# schBeagleBone.net
KiCad netlist of a schematic drawn in Altium Designer
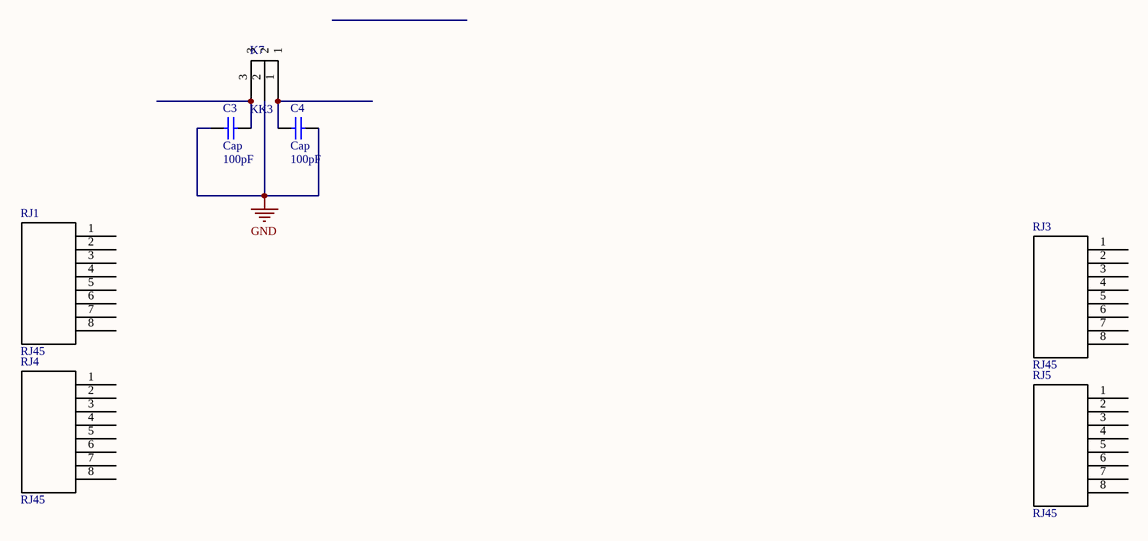
[diagram p0: schBeagleBone.SchDoc]

(export (version "E")
  (design (tool "Eeschema 10.0.6"))
  (components
    (comp (ref "C3")
      (value "Cap")
      (footprint "RAD-0.3")
      (description "Capacitor")
      (fields (field (name "ALTIUM_VALUE") "100pF") (field (name "PUBLISHER") "Altium Limited"))
      (libsource (lib "Miscellaneous Devices") (part "Cap"))
    )
    (comp (ref "C4")
      (value "Cap")
      (footprint "RAD-0.3")
      (description "Capacitor")
      (fields (field (name "ALTIUM_VALUE") "100pF") (field (name "PUBLISHER") "Altium Limited"))
      (libsource (lib "Miscellaneous Devices") (part "Cap"))
    )
    (comp (ref "K7") (value "KK3") (footprint "3-vias") (libsource (lib "Componentes_Open") (part "KK3Vias")))
    (comp (ref "RJ1")
      (value "RJ45")
      (footprint "RJ45_90")
      (libsource (lib "Componentes_Open") (part "RJ45_90"))
    )
    (comp (ref "RJ3")
      (value "RJ45")
      (footprint "RJ45_Simples")
      (libsource (lib "Componentes_Open") (part "RJ45"))
    )
    (comp (ref "RJ4")
      (value "RJ45")
      (footprint "RJ45_90")
      (libsource (lib "Componentes_Open") (part "RJ45_90"))
    )
    (comp (ref "RJ5")
      (value "RJ45")
      (footprint "RJ45_Simples")
      (libsource (lib "Componentes_Open") (part "RJ45"))
    )
  )
  (nets
    (net (code "1") (name "GND") (class "Default")
      (node (ref "C3") (pin "1") (pinfunction "1_1") (pintype "passive"))
      (node (ref "C4") (pin "2") (pinfunction "2_2") (pintype "passive"))
      (node (ref "K7") (pin "2") (pinfunction "2_2") (pintype "passive"))
    )
    (net (code "2") (name "Net-(C3-Pad2)") (class "Default")
      (node (ref "C3") (pin "2") (pinfunction "2_2") (pintype "passive"))
      (node (ref "K7") (pin "3") (pinfunction "3_3") (pintype "passive"))
    )
    (net (code "3") (name "Net-(C4-Pad1)") (class "Default")
      (node (ref "C4") (pin "1") (pinfunction "1_1") (pintype "passive"))
      (node (ref "K7") (pin "1") (pinfunction "1_1") (pintype "passive"))
    )
    (net (code "4") (name "unconnected-(RJ1-9-Pad1)") (class "Default")
      (node (ref "RJ1") (pin "1") (pinfunction "9_1") (pintype "passive"))
    )
    (net (code "5") (name "unconnected-(RJ1-Pad2)") (class "Default")
      (node (ref "RJ1") (pin "2") (pinfunction "2_2") (pintype "passive"))
    )
    (net (code "6") (name "unconnected-(RJ1-Pad3)") (class "Default")
      (node (ref "RJ1") (pin "3") (pinfunction "3_3") (pintype "passive"))
    )
    (net (code "7") (name "unconnected-(RJ1-Pad4)") (class "Default")
      (node (ref "RJ1") (pin "4") (pinfunction "4_4") (pintype "passive"))
    )
    (net (code "8") (name "unconnected-(RJ1-Pad5)") (class "Default")
      (node (ref "RJ1") (pin "5") (pinfunction "5_5") (pintype "passive"))
    )
    (net (code "9") (name "unconnected-(RJ1-Pad6)") (class "Default")
      (node (ref "RJ1") (pin "6") (pinfunction "6_6") (pintype "passive"))
    )
    (net (code "10") (name "unconnected-(RJ1-Pad7)") (class "Default")
      (node (ref "RJ1") (pin "7") (pinfunction "7_7") (pintype "passive"))
    )
    (net (code "11") (name "unconnected-(RJ1-Pad8)") (class "Default")
      (node (ref "RJ1") (pin "8") (pinfunction "8_8") (pintype "passive"))
    )
    (net (code "12") (name "unconnected-(RJ3-9-Pad1)") (class "Default")
      (node (ref "RJ3") (pin "1") (pinfunction "9_1") (pintype "passive"))
    )
    (net (code "13") (name "unconnected-(RJ3-Pad2)") (class "Default")
      (node (ref "RJ3") (pin "2") (pinfunction "2_2") (pintype "passive"))
    )
    (net (code "14") (name "unconnected-(RJ3-Pad3)") (class "Default")
      (node (ref "RJ3") (pin "3") (pinfunction "3_3") (pintype "passive"))
    )
    (net (code "15") (name "unconnected-(RJ3-Pad4)") (class "Default")
      (node (ref "RJ3") (pin "4") (pinfunction "4_4") (pintype "passive"))
    )
    (net (code "16") (name "unconnected-(RJ3-Pad5)") (class "Default")
      (node (ref "RJ3") (pin "5") (pinfunction "5_5") (pintype "passive"))
    )
    (net (code "17") (name "unconnected-(RJ3-Pad6)") (class "Default")
      (node (ref "RJ3") (pin "6") (pinfunction "6_6") (pintype "passive"))
    )
    (net (code "18") (name "unconnected-(RJ3-Pad7)") (class "Default")
      (node (ref "RJ3") (pin "7") (pinfunction "7_7") (pintype "passive"))
    )
    (net (code "19") (name "unconnected-(RJ3-Pad8)") (class "Default")
      (node (ref "RJ3") (pin "8") (pinfunction "8_8") (pintype "passive"))
    )
    (net (code "20") (name "unconnected-(RJ4-9-Pad1)") (class "Default")
      (node (ref "RJ4") (pin "1") (pinfunction "9_1") (pintype "passive"))
    )
    (net (code "21") (name "unconnected-(RJ4-Pad2)") (class "Default")
      (node (ref "RJ4") (pin "2") (pinfunction "2_2") (pintype "passive"))
    )
    (net (code "22") (name "unconnected-(RJ4-Pad3)") (class "Default")
      (node (ref "RJ4") (pin "3") (pinfunction "3_3") (pintype "passive"))
    )
    (net (code "23") (name "unconnected-(RJ4-Pad4)") (class "Default")
      (node (ref "RJ4") (pin "4") (pinfunction "4_4") (pintype "passive"))
    )
    (net (code "24") (name "unconnected-(RJ4-Pad5)") (class "Default")
      (node (ref "RJ4") (pin "5") (pinfunction "5_5") (pintype "passive"))
    )
    (net (code "25") (name "unconnected-(RJ4-Pad6)") (class "Default")
      (node (ref "RJ4") (pin "6") (pinfunction "6_6") (pintype "passive"))
    )
    (net (code "26") (name "unconnected-(RJ4-Pad7)") (class "Default")
      (node (ref "RJ4") (pin "7") (pinfunction "7_7") (pintype "passive"))
    )
    (net (code "27") (name "unconnected-(RJ4-Pad8)") (class "Default")
      (node (ref "RJ4") (pin "8") (pinfunction "8_8") (pintype "passive"))
    )
    (net (code "28") (name "unconnected-(RJ5-9-Pad1)") (class "Default")
      (node (ref "RJ5") (pin "1") (pinfunction "9_1") (pintype "passive"))
    )
    (net (code "29") (name "unconnected-(RJ5-Pad2)") (class "Default")
      (node (ref "RJ5") (pin "2") (pinfunction "2_2") (pintype "passive"))
    )
    (net (code "30") (name "unconnected-(RJ5-Pad3)") (class "Default")
      (node (ref "RJ5") (pin "3") (pinfunction "3_3") (pintype "passive"))
    )
    (net (code "31") (name "unconnected-(RJ5-Pad4)") (class "Default")
      (node (ref "RJ5") (pin "4") (pinfunction "4_4") (pintype "passive"))
    )
    (net (code "32") (name "unconnected-(RJ5-Pad5)") (class "Default")
      (node (ref "RJ5") (pin "5") (pinfunction "5_5") (pintype "passive"))
    )
    (net (code "33") (name "unconnected-(RJ5-Pad6)") (class "Default")
      (node (ref "RJ5") (pin "6") (pinfunction "6_6") (pintype "passive"))
    )
    (net (code "34") (name "unconnected-(RJ5-Pad7)") (class "Default")
      (node (ref "RJ5") (pin "7") (pinfunction "7_7") (pintype "passive"))
    )
    (net (code "35") (name "unconnected-(RJ5-Pad8)") (class "Default")
      (node (ref "RJ5") (pin "8") (pinfunction "8_8") (pintype "passive"))
    )
  )
)
